# StepStick-Protector_v11.net
KiCad netlist of a schematic drawn in EAGLE
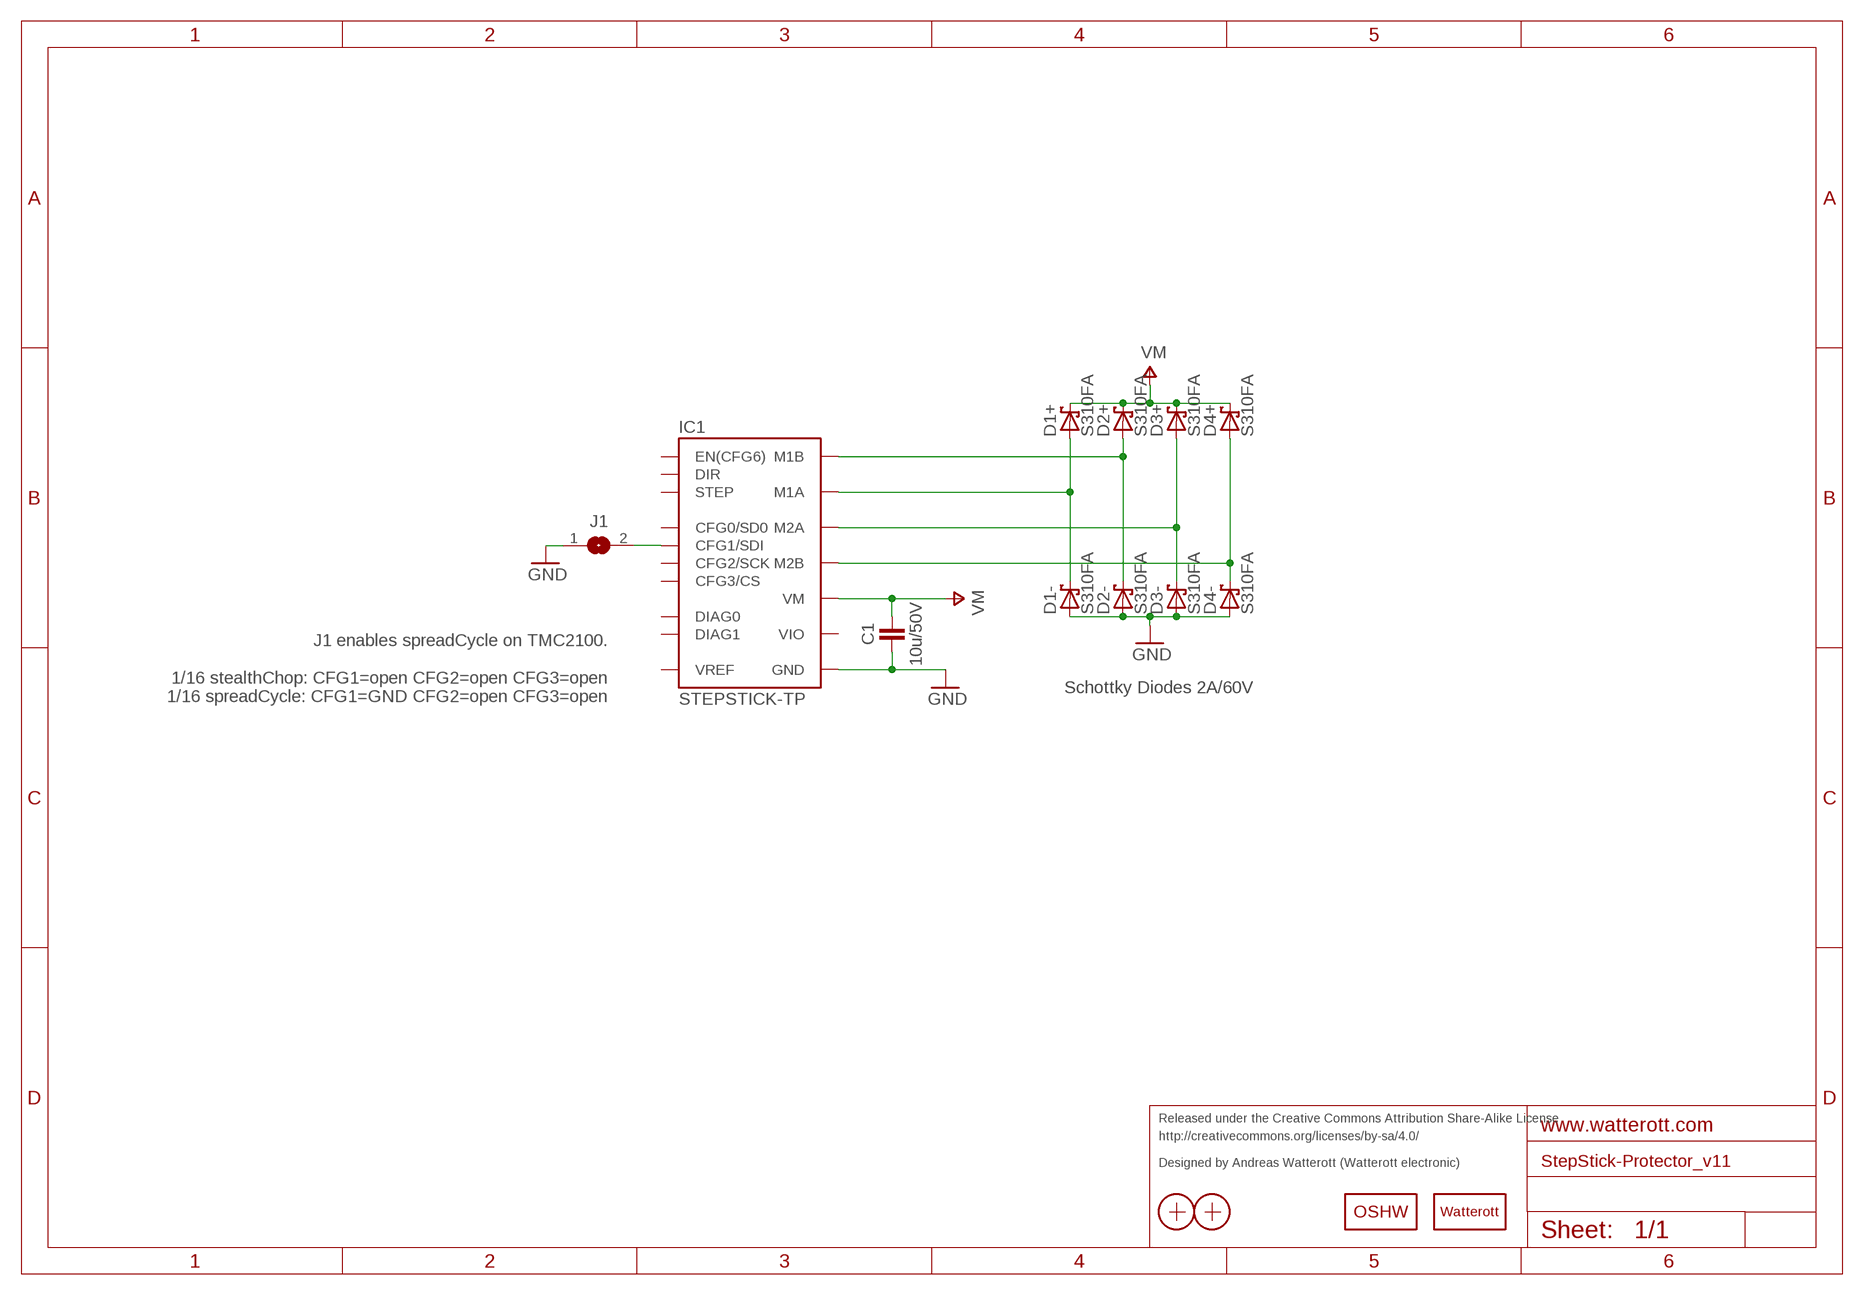
[diagram p0: schematic, sheet 1]

(export (version "E")
  (design (tool "Eeschema 10.0.6"))
  (components
    (comp (ref "C1")
      (value "10u/50V")
      (footprint "eagle-import:C1210")
      (libsource (lib "eagle-import") (part "CAPACITOR-1210"))
    )
    (comp (ref "D1+")
      (value "S310FA")
      (footprint "eagle-import:SOD123")
      (libsource (lib "eagle-import") (part "D_SCHOTTKY-SOD123"))
    )
    (comp (ref "D1-")
      (value "S310FA")
      (footprint "eagle-import:SOD123")
      (libsource (lib "eagle-import") (part "D_SCHOTTKY-SOD123"))
    )
    (comp (ref "D2+")
      (value "S310FA")
      (footprint "eagle-import:SOD123")
      (libsource (lib "eagle-import") (part "D_SCHOTTKY-SOD123"))
    )
    (comp (ref "D2-")
      (value "S310FA")
      (footprint "eagle-import:SOD123")
      (libsource (lib "eagle-import") (part "D_SCHOTTKY-SOD123"))
    )
    (comp (ref "D3+")
      (value "S310FA")
      (footprint "eagle-import:SOD123")
      (libsource (lib "eagle-import") (part "D_SCHOTTKY-SOD123"))
    )
    (comp (ref "D3-")
      (value "S310FA")
      (footprint "eagle-import:SOD123")
      (libsource (lib "eagle-import") (part "D_SCHOTTKY-SOD123"))
    )
    (comp (ref "D4+")
      (value "S310FA")
      (footprint "eagle-import:SOD123")
      (libsource (lib "eagle-import") (part "D_SCHOTTKY-SOD123"))
    )
    (comp (ref "D4-")
      (value "S310FA")
      (footprint "eagle-import:SOD123")
      (libsource (lib "eagle-import") (part "D_SCHOTTKY-SOD123"))
    )
    (comp (ref "IC1")
      (value "STEPSTICK-TP")
      (footprint "eagle-import:STEPSTICK_TP")
      (libsource (lib "eagle-import") (part "STEPSTICK-TP"))
    )
    (comp (ref "J1")
      (value "JUMPER2-0603-NC")
      (footprint "eagle-import:JUMPER2-0603_NC")
      (libsource (lib "eagle-import") (part "JUMPER2-0603-NC"))
    )
    (comp (ref "LOGO1")
      (value "OSHW_LOGOX0070")
      (footprint "eagle-import:OSHW_6X70")
      (libsource (lib "eagle-import") (part "OSHW_LOGOX0070"))
    )
    (comp (ref "LOGO2")
      (value "LOGO-S_PLACE_S")
      (footprint "eagle-import:SPARK_TPLACE_S")
      (libsource (lib "eagle-import") (part "LOGO-S_PLACE_S"))
    )
    (comp (ref "X1")
      (value "PASSER")
      (footprint "eagle-import:PASSER")
      (libsource (lib "eagle-import") (part "PASSER"))
    )
    (comp (ref "X2")
      (value "PASSER")
      (footprint "eagle-import:PASSER")
      (libsource (lib "eagle-import") (part "PASSER"))
    )
  )
  (nets
    (net (code "1") (name "/VIO") (class "Default")
      (node (ref "IC1") (pin "VIO") (pinfunction "VIO_VIO") (pintype "power_in"))
    )
    (net (code "2") (name "GND") (class "Default")
      (node (ref "C1") (pin "1") (pinfunction "1_1") (pintype "passive"))
      (node (ref "D1-") (pin "A") (pinfunction "A_A") (pintype "passive"))
      (node (ref "D2-") (pin "A") (pinfunction "A_A") (pintype "passive"))
      (node (ref "D3-") (pin "A") (pinfunction "A_A") (pintype "passive"))
      (node (ref "D4-") (pin "A") (pinfunction "A_A") (pintype "passive"))
      (node (ref "IC1") (pin "GND@1") (pinfunction "GND_GND@1") (pintype "power_in"))
      (node (ref "IC1") (pin "GND@2") (pinfunction "GND_GND@2") (pintype "power_in"))
      (node (ref "J1") (pin "1") (pinfunction "1_1") (pintype "passive"))
    )
    (net (code "3") (name "Net-(D1+-PadA)") (class "Default")
      (node (ref "D1+") (pin "A") (pinfunction "A_A") (pintype "passive"))
      (node (ref "D1-") (pin "C") (pinfunction "C_C") (pintype "passive"))
      (node (ref "IC1") (pin "M1A") (pinfunction "M1A_M1A") (pintype "output"))
    )
    (net (code "4") (name "Net-(D2+-PadA)") (class "Default")
      (node (ref "D2+") (pin "A") (pinfunction "A_A") (pintype "passive"))
      (node (ref "D2-") (pin "C") (pinfunction "C_C") (pintype "passive"))
      (node (ref "IC1") (pin "M1B") (pinfunction "M1B_M1B") (pintype "output"))
    )
    (net (code "5") (name "Net-(D3+-PadA)") (class "Default")
      (node (ref "D3+") (pin "A") (pinfunction "A_A") (pintype "passive"))
      (node (ref "D3-") (pin "C") (pinfunction "C_C") (pintype "passive"))
      (node (ref "IC1") (pin "M2A") (pinfunction "M2A_M2A") (pintype "output"))
    )
    (net (code "6") (name "Net-(D4+-PadA)") (class "Default")
      (node (ref "D4+") (pin "A") (pinfunction "A_A") (pintype "passive"))
      (node (ref "D4-") (pin "C") (pinfunction "C_C") (pintype "passive"))
      (node (ref "IC1") (pin "M2B") (pinfunction "M2B_M2B") (pintype "output"))
    )
    (net (code "7") (name "Net-(IC1-CFG1{slash}SDI)") (class "Default")
      (node (ref "IC1") (pin "CFG1") (pinfunction "CFG1/SDI_CFG1") (pintype "bidirectional"))
      (node (ref "J1") (pin "2") (pinfunction "2_2") (pintype "passive"))
    )
    (net (code "8") (name "VM") (class "Default")
      (node (ref "C1") (pin "2") (pinfunction "2_2") (pintype "passive"))
      (node (ref "D1+") (pin "C") (pinfunction "C_C") (pintype "passive"))
      (node (ref "D2+") (pin "C") (pinfunction "C_C") (pintype "passive"))
      (node (ref "D3+") (pin "C") (pinfunction "C_C") (pintype "passive"))
      (node (ref "D4+") (pin "C") (pinfunction "C_C") (pintype "passive"))
      (node (ref "IC1") (pin "VM") (pinfunction "VM_VM") (pintype "power_in"))
    )
    (net (code "9") (name "unconnected-(IC1-CFG0{slash}SD0-PadNC{slash}CFG0)") (class "Default")
      (node (ref "IC1") (pin "NC/CFG0") (pinfunction "CFG0/SD0_NC/CFG0") (pintype "bidirectional"))
    )
    (net (code "10") (name "unconnected-(IC1-CFG2{slash}SCK-PadCFG2)") (class "Default")
      (node (ref "IC1") (pin "CFG2") (pinfunction "CFG2/SCK_CFG2") (pintype "bidirectional"))
    )
    (net (code "11") (name "unconnected-(IC1-CFG3{slash}CS-PadCFG3)") (class "Default")
      (node (ref "IC1") (pin "CFG3") (pinfunction "CFG3/CS_CFG3") (pintype "bidirectional"))
    )
    (net (code "12") (name "unconnected-(IC1-EN(CFG6)-PadEN)") (class "Default")
      (node (ref "IC1") (pin "EN") (pinfunction "EN(CFG6)_EN") (pintype "bidirectional"))
    )
    (net (code "13") (name "unconnected-(IC1-PadDIAG0)") (class "Default")
      (node (ref "IC1") (pin "DIAG0") (pinfunction "DIAG0_DIAG0") (pintype "bidirectional"))
    )
    (net (code "14") (name "unconnected-(IC1-PadDIAG1)") (class "Default")
      (node (ref "IC1") (pin "DIAG1") (pinfunction "DIAG1_DIAG1") (pintype "bidirectional"))
    )
    (net (code "15") (name "unconnected-(IC1-PadDIR)") (class "Default")
      (node (ref "IC1") (pin "DIR") (pinfunction "DIR_DIR") (pintype "bidirectional"))
    )
    (net (code "16") (name "unconnected-(IC1-PadSTEP)") (class "Default")
      (node (ref "IC1") (pin "STEP") (pinfunction "STEP_STEP") (pintype "bidirectional"))
    )
    (net (code "17") (name "unconnected-(IC1-PadVREF)") (class "Default")
      (node (ref "IC1") (pin "VREF") (pinfunction "VREF_VREF") (pintype "passive"))
    )
  )
)
